# display.net
KiCad netlist of a schematic drawn in Altium Designer
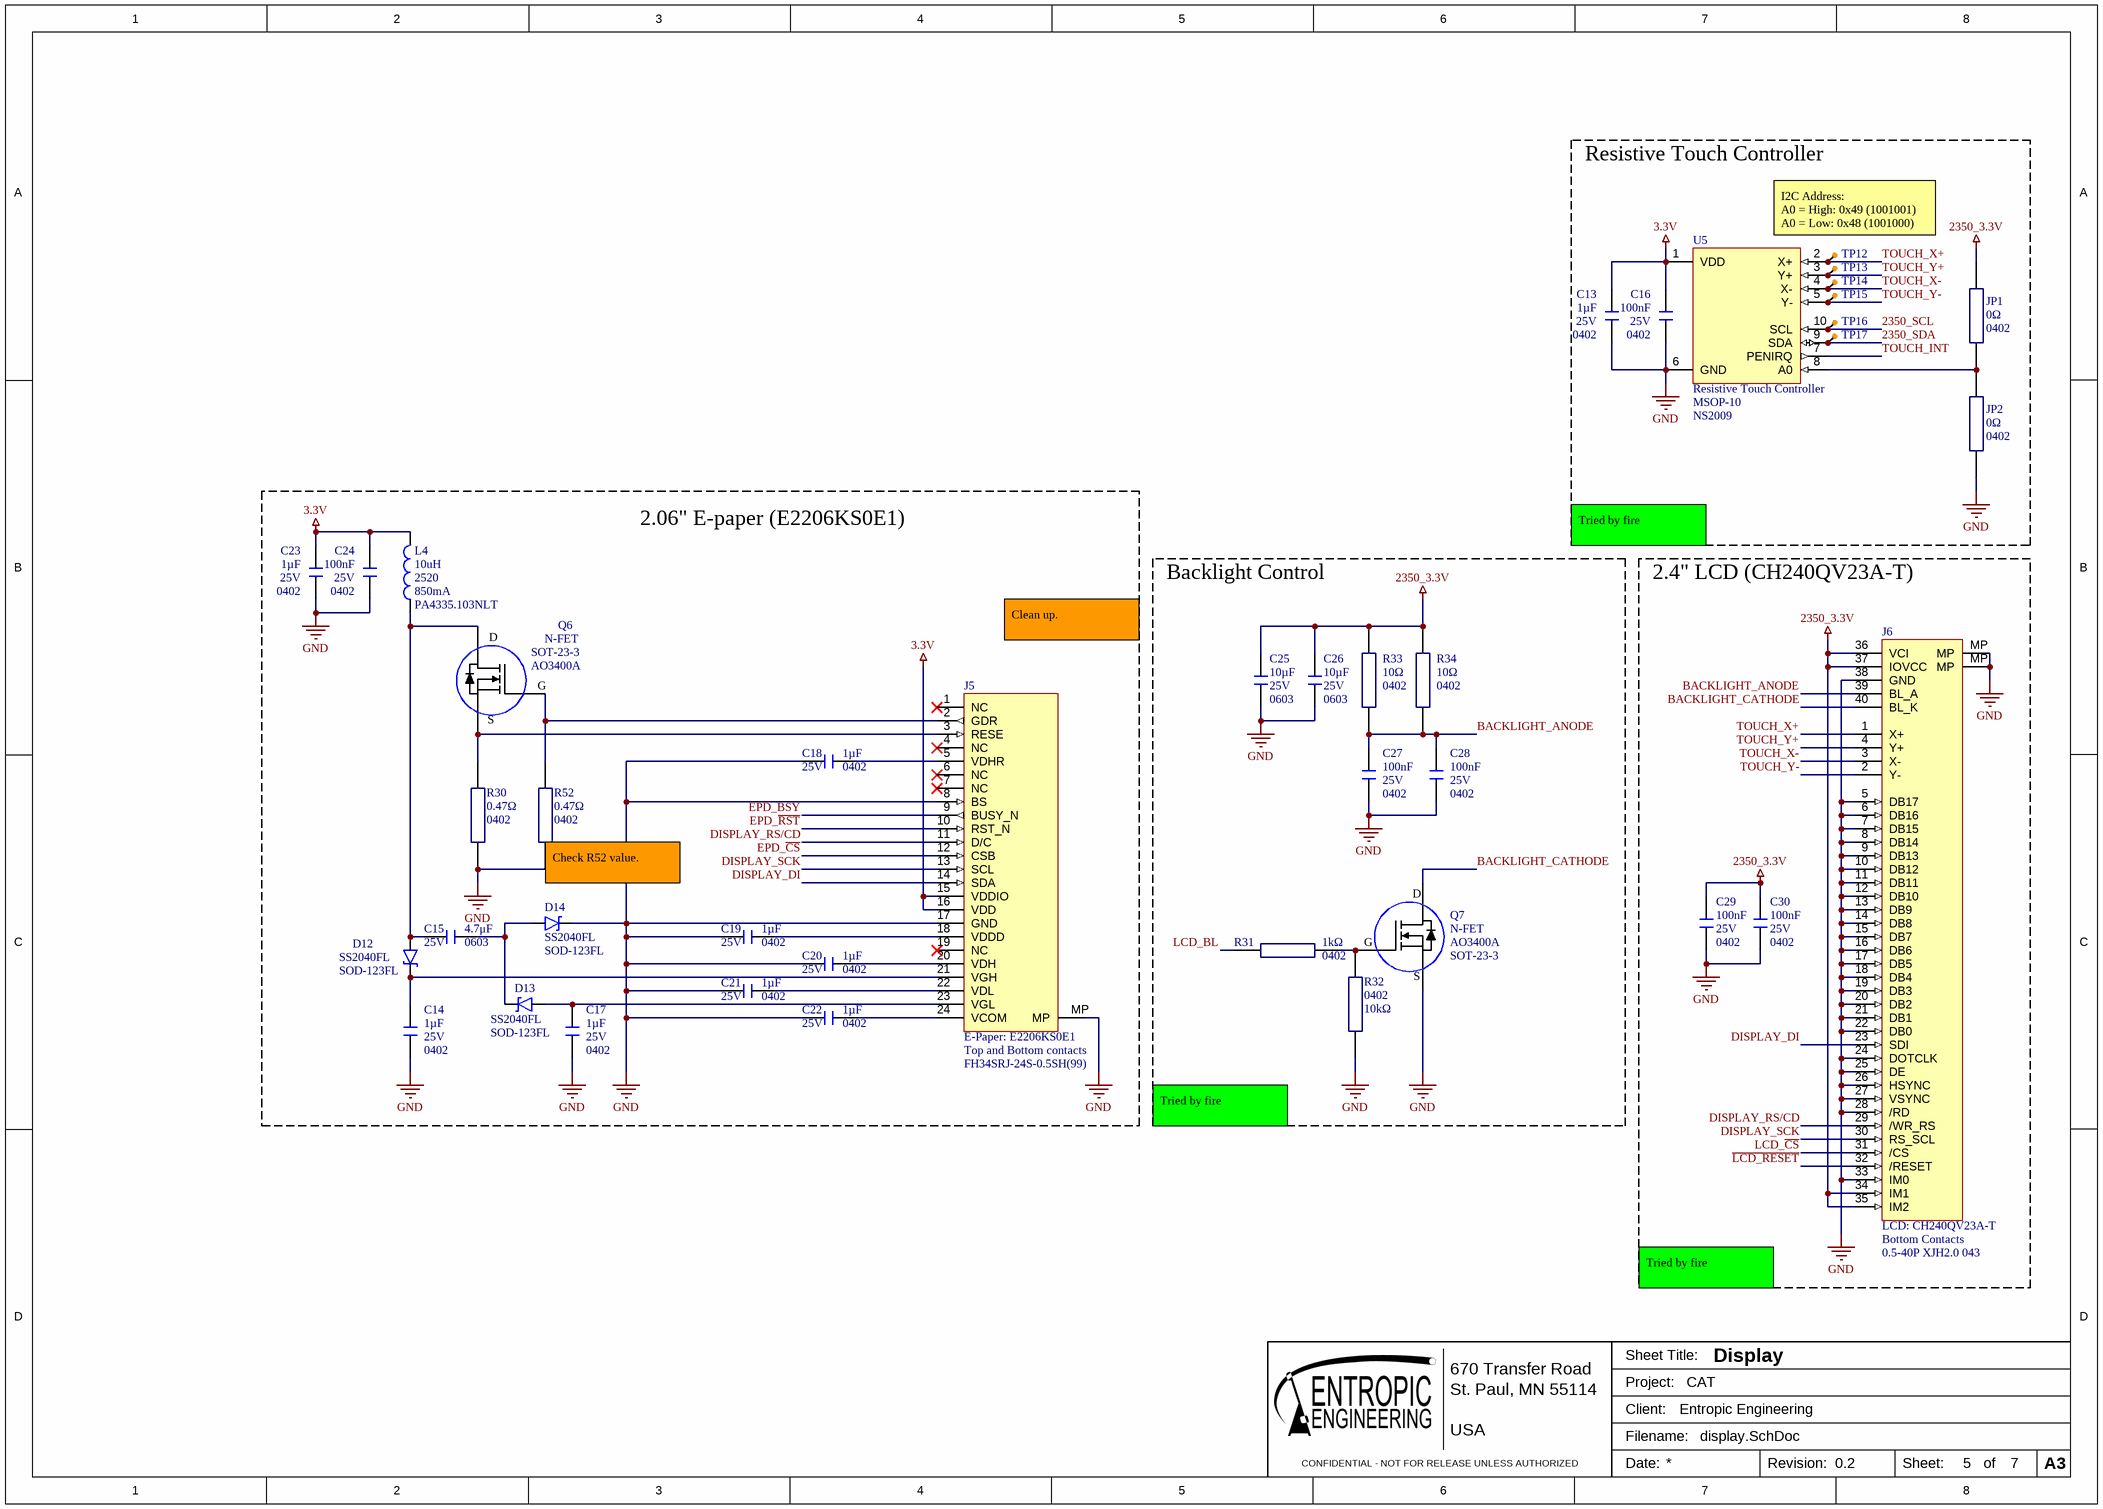
[diagram p0: display.SchDoc]

(export (version "E")
  (design (tool "Eeschema 10.0.6"))
  (components
    (comp (ref "C13")
      (value "GRM155R61E105KA12D")
      (footprint "0402_capacitor")
      (description "1 µF, 25 V, X5R, 0402 Chip capacitor")
      (fields
        (field (name "MANUFACTURER") "Murata")
        (field (name "HOUSE_PART_NUMBER") "C-1uF-0402-002")
        (field (name "SIZE CODE") "0402")
        (field (name "CAPACITANCE") "1µF")
        (field (name "VOLTAGE") "25V")
      )
      (libsource (lib "cat") (part "GRM155R61E105KA12D"))
    )
    (comp (ref "C14")
      (value "GRM155R61E105KA12D")
      (footprint "0402_capacitor")
      (description "1 µF, 25 V, X5R, 0402 Chip capacitor")
      (fields
        (field (name "MANUFACTURER") "Murata")
        (field (name "HOUSE_PART_NUMBER") "C-1uF-0402-002")
        (field (name "SIZE CODE") "0402")
        (field (name "CAPACITANCE") "1µF")
        (field (name "VOLTAGE") "25V")
      )
      (libsource (lib "cat") (part "GRM155R61E105KA12D"))
    )
    (comp (ref "C15")
      (value "4.7μF")
      (footprint "0603_capacitor")
      (description "4.7 μF, 25 V, X7R, 0603 Chip capacitor")
      (fields
        (field (name "MANUFACTURER") "TDK")
        (field (name "MANUFACTURER PART NUMBER") "C1608X5R1E475K080AC")
        (field (name "VOLTAGE RATING") "25V")
        (field (name "CASE/PACKAGE") "0603")
      )
      (libsource (lib "cat") (part "C1608X5R1E475K080AC"))
    )
    (comp (ref "C16")
      (value "GRM155R71E104KE14D")
      (footprint "0402_capacitor")
      (description "100 nF, 25 V, X7R, 0402 Chip capacitor")
      (fields
        (field (name "MANUFACTURER") "Murata")
        (field (name "TOLERANCE") "10%")
        (field (name "CASE CODE (IMPERIAL)") "0402")
        (field (name "VOLTAGE") "25V")
        (field (name "CAPACITANCE") "100nF")
      )
      (libsource (lib "") (part "GRM155R71E104KE14D_1"))
    )
    (comp (ref "C17")
      (value "GRM155R61E105KA12D")
      (footprint "0402_capacitor")
      (description "1 µF, 25 V, X5R, 0402 Chip capacitor")
      (fields
        (field (name "MANUFACTURER") "Murata")
        (field (name "HOUSE_PART_NUMBER") "C-1uF-0402-002")
        (field (name "SIZE CODE") "0402")
        (field (name "CAPACITANCE") "1µF")
        (field (name "VOLTAGE") "25V")
      )
      (libsource (lib "cat") (part "GRM155R61E105KA12D"))
    )
    (comp (ref "C18")
      (value "GRM155R61E105KA12D")
      (footprint "0402_capacitor")
      (description "1 µF, 25 V, X5R, 0402 Chip capacitor")
      (fields
        (field (name "MANUFACTURER") "Murata")
        (field (name "HOUSE_PART_NUMBER") "C-1uF-0402-002")
        (field (name "SIZE CODE") "0402")
        (field (name "CAPACITANCE") "1µF")
        (field (name "VOLTAGE") "25V")
      )
      (libsource (lib "cat") (part "GRM155R61E105KA12D"))
    )
    (comp (ref "C19")
      (value "GRM155R61E105KA12D")
      (footprint "0402_capacitor")
      (description "1 µF, 25 V, X5R, 0402 Chip capacitor")
      (fields
        (field (name "MANUFACTURER") "Murata")
        (field (name "HOUSE_PART_NUMBER") "C-1uF-0402-002")
        (field (name "SIZE CODE") "0402")
        (field (name "CAPACITANCE") "1µF")
        (field (name "VOLTAGE") "25V")
      )
      (libsource (lib "cat") (part "GRM155R61E105KA12D"))
    )
    (comp (ref "C20")
      (value "GRM155R61E105KA12D")
      (footprint "0402_capacitor")
      (description "1 µF, 25 V, X5R, 0402 Chip capacitor")
      (fields
        (field (name "MANUFACTURER") "Murata")
        (field (name "HOUSE_PART_NUMBER") "C-1uF-0402-002")
        (field (name "SIZE CODE") "0402")
        (field (name "CAPACITANCE") "1µF")
        (field (name "VOLTAGE") "25V")
      )
      (libsource (lib "cat") (part "GRM155R61E105KA12D"))
    )
    (comp (ref "C21")
      (value "GRM155R61E105KA12D")
      (footprint "0402_capacitor")
      (description "1 µF, 25 V, X5R, 0402 Chip capacitor")
      (fields
        (field (name "MANUFACTURER") "Murata")
        (field (name "HOUSE_PART_NUMBER") "C-1uF-0402-002")
        (field (name "SIZE CODE") "0402")
        (field (name "CAPACITANCE") "1µF")
        (field (name "VOLTAGE") "25V")
      )
      (libsource (lib "cat") (part "GRM155R61E105KA12D"))
    )
    (comp (ref "C22")
      (value "GRM155R61E105KA12D")
      (footprint "0402_capacitor")
      (description "1 µF, 25 V, X5R, 0402 Chip capacitor")
      (fields
        (field (name "MANUFACTURER") "Murata")
        (field (name "HOUSE_PART_NUMBER") "C-1uF-0402-002")
        (field (name "SIZE CODE") "0402")
        (field (name "CAPACITANCE") "1µF")
        (field (name "VOLTAGE") "25V")
      )
      (libsource (lib "cat") (part "GRM155R61E105KA12D"))
    )
    (comp (ref "C23")
      (value "GRM155R61E105KA12D")
      (footprint "0402_capacitor")
      (description "1 µF, 25 V, X5R, 0402 Chip capacitor")
      (fields
        (field (name "MANUFACTURER") "Murata")
        (field (name "HOUSE_PART_NUMBER") "C-1uF-0402-002")
        (field (name "SIZE CODE") "0402")
        (field (name "CAPACITANCE") "1µF")
        (field (name "VOLTAGE") "25V")
      )
      (libsource (lib "cat") (part "GRM155R61E105KA12D"))
    )
    (comp (ref "C24")
      (value "GRM155R71E104KE14D")
      (footprint "0402_capacitor")
      (description "100 nF, 25 V, X7R, 0402 Chip capacitor")
      (fields
        (field (name "MANUFACTURER") "Murata")
        (field (name "TOLERANCE") "10%")
        (field (name "CASE CODE (IMPERIAL)") "0402")
        (field (name "VOLTAGE") "25V")
        (field (name "CAPACITANCE") "100nF")
      )
      (libsource (lib "") (part "GRM155R71E104KE14D_1"))
    )
    (comp (ref "C25")
      (value "10µF")
      (footprint "0603_capacitor")
      (description "10 µF, 25 V, X5R, 0603 Chip capacitor")
      (fields
        (field (name "MANUFACTURER") "Samsung")
        (field (name "CASE/PACKAGE") "0603")
        (field (name "TOLERANCE") "20%")
        (field (name "VOLTAGE RATING") "25V")
      )
      (libsource (lib "cat") (part "CL10A106MA8NRNC"))
    )
    (comp (ref "C26")
      (value "10µF")
      (footprint "0603_capacitor")
      (description "10 µF, 25 V, X5R, 0603 Chip capacitor")
      (fields
        (field (name "MANUFACTURER") "Samsung")
        (field (name "CASE/PACKAGE") "0603")
        (field (name "TOLERANCE") "20%")
        (field (name "VOLTAGE RATING") "25V")
      )
      (libsource (lib "cat") (part "CL10A106MA8NRNC"))
    )
    (comp (ref "C27")
      (value "GRM155R71E104KE14D")
      (footprint "0402_capacitor")
      (description "100 nF, 25 V, X7R, 0402 Chip capacitor")
      (fields
        (field (name "MANUFACTURER") "Murata")
        (field (name "TOLERANCE") "10%")
        (field (name "CASE CODE (IMPERIAL)") "0402")
        (field (name "VOLTAGE") "25V")
        (field (name "CAPACITANCE") "100nF")
      )
      (libsource (lib "cat") (part "GRM155R71E104KE14D"))
    )
    (comp (ref "C28")
      (value "GRM155R71E104KE14D")
      (footprint "0402_capacitor")
      (description "100 nF, 25 V, X7R, 0402 Chip capacitor")
      (fields
        (field (name "MANUFACTURER") "Murata")
        (field (name "TOLERANCE") "10%")
        (field (name "CASE CODE (IMPERIAL)") "0402")
        (field (name "VOLTAGE") "25V")
        (field (name "CAPACITANCE") "100nF")
      )
      (libsource (lib "cat") (part "GRM155R71E104KE14D"))
    )
    (comp (ref "C29")
      (value "GRM155R71E104KE14D")
      (footprint "0402_capacitor")
      (description "100 nF, 25 V, X7R, 0402 Chip capacitor")
      (fields
        (field (name "MANUFACTURER") "Murata")
        (field (name "TOLERANCE") "10%")
        (field (name "CASE CODE (IMPERIAL)") "0402")
        (field (name "VOLTAGE") "25V")
        (field (name "CAPACITANCE") "100nF")
      )
      (libsource (lib "cat") (part "GRM155R71E104KE14D"))
    )
    (comp (ref "C30")
      (value "GRM155R71E104KE14D")
      (footprint "0402_capacitor")
      (description "100 nF, 25 V, X7R, 0402 Chip capacitor")
      (fields
        (field (name "MANUFACTURER") "Murata")
        (field (name "TOLERANCE") "10%")
        (field (name "CASE CODE (IMPERIAL)") "0402")
        (field (name "VOLTAGE") "25V")
        (field (name "CAPACITANCE") "100nF")
      )
      (libsource (lib "cat") (part "GRM155R71E104KE14D"))
    )
    (comp (ref "D12")
      (value "SS2040FL")
      (footprint "SOD-123")
      (description "Schottky-diode 2A 40V SOD123FL")
      (fields
        (field (name "MANUFACTURER") "Pan Jit")
        (field (name "MANUFACTURER PART NUMBER") "SS2040FL_R1_00001")
        (field (name "CASE/PACKAGE") "SOD-123FL")
      )
      (libsource (lib "cat") (part "SS2040FL_R1_00001"))
    )
    (comp (ref "D13")
      (value "SS2040FL")
      (footprint "SOD-123")
      (description "Schottky-diode 2A 40V SOD123FL")
      (fields
        (field (name "MANUFACTURER") "Pan Jit")
        (field (name "MANUFACTURER PART NUMBER") "SS2040FL_R1_00001")
        (field (name "CASE/PACKAGE") "SOD-123FL")
      )
      (libsource (lib "cat") (part "SS2040FL_R1_00001"))
    )
    (comp (ref "D14")
      (value "SS2040FL")
      (footprint "SOD-123")
      (description "Schottky-diode 2A 40V SOD123FL")
      (fields
        (field (name "MANUFACTURER") "Pan Jit")
        (field (name "MANUFACTURER PART NUMBER") "SS2040FL_R1_00001")
        (field (name "CASE/PACKAGE") "SOD-123FL")
      )
      (libsource (lib "cat") (part "SS2040FL_R1_00001"))
    )
    (comp (ref "J5")
      (value "E-Paper: E2206KS0E1")
      (footprint "E2206KS0E1")
      (description "24-Pin FPC Connector, 0.5mm pitch for E2206KS0E1 E-Paper display")
      (fields
        (field (name "MANUFACTURER") "Hirose")
        (field (name "CONTACT_SIDE") "Top and Bottom contacts")
        (field (name "MANUFACTURER PART NUMBER") "FH34SRJ-24S-0.5SH(99)")
      )
      (libsource (lib "cat") (part "FH34SRJ-24S-0.5SH"))
    )
    (comp (ref "J6")
      (value "LCD: CH240QV23A-T")
      (footprint "CH240QV23A-T")
      (description "40-Pin, 0.5 mm pitch, bottom contact, flat flex connector for LCD CH240QV23A-T")
      (fields
        (field (name "LCD PART NUMBER") "CH240QV23A-T")
        (field (name "CONTACT_SIDE") "Bottom Contacts")
        (field (name "MANUFACTURER PART NUMBER") "0.5-40P XJH2.0 043")
        (field (name "HOUSE_PART_NUMBER") "0.5-40P XJH2.0 043")
      )
      (libsource (lib "cat") (part "0.5-40P XJH2.0 043"))
    )
    (comp (ref "JP1")
      (value "0Ω")
      (footprint "0402_resistor")
      (description "0 Ω, 0402 Chip resistor (jumper)")
      (fields
        (field (name "MANUFACTURER") "Yageo")
        (field (name "MANUFACTURER PART NUMBER") "RC0402FR-070RL")
        (field (name "CASE/PACKAGE") "0402")
      )
      (libsource (lib "cat") (part "RC0402FR-070RL"))
    )
    (comp (ref "JP2")
      (value "0Ω")
      (footprint "0402_resistor")
      (description "0 Ω, 0402 Chip resistor (jumper)")
      (fields
        (field (name "MANUFACTURER") "Yageo")
        (field (name "MANUFACTURER PART NUMBER") "RC0402FR-070RL")
        (field (name "CASE/PACKAGE") "0402")
      )
      (libsource (lib "cat") (part "RC0402FR-070RL"))
    )
    (comp (ref "L4")
      (value "10uH")
      (footprint "INDC2520X12N")
      (description "Drum Core Shielded Power Inductor Wirewound Ferrite 10uH 20% 1MHz 0.85A SMD T/R")
      (fields
        (field (name "MANUFACTURER") "Pulse")
        (field (name "CASE/PACKAGE") "2520")
        (field (name "TOLERANCE") "20%")
        (field (name "CURRENT RATING") "850mA")
        (field (name "MANUFACTURER PART NUMBER") "PA4335.103NLT")
      )
      (libsource (lib "cat") (part "PA4335.103NLT"))
    )
    (comp (ref "Q6")
      (value "N-FET")
      (footprint "SOT95P280X115-3N")
      (description "N-FET, 30V, 5.7A, SOT-23-3")
      (fields
        (field (name "MANUFACTURER") "Alpha & Omega Semiconductor")
        (field (name "HOUSE_PART_NUMBER") "AO3400A")
        (field (name "CASE/PACKAGE") "SOT-23-3")
        (field (name "MANUFACTURER PART NUMBER") "AO3400A")
      )
      (libsource (lib "cat") (part "AO3400A"))
    )
    (comp (ref "Q7")
      (value "N-FET")
      (footprint "SOT95P280X115-3N")
      (description "N-FET, 30V, 5.7A, SOT-23-3")
      (fields
        (field (name "MANUFACTURER") "Alpha & Omega Semiconductor")
        (field (name "CASE/PACKAGE") "SOT-23-3")
        (field (name "MANUFACTURER PART NUMBER") "AO3400A")
        (field (name "HOUSE_PART_NUMBER") "AO3400A")
      )
      (libsource (lib "cat") (part "AO3400A"))
    )
    (comp (ref "R30")
      (value "0.47Ω")
      (footprint "0402_resistor")
      (description "0.47Ω, 1% 0402 Chip resistor")
      (fields
        (field (name "MANUFACTURER") "Yageo")
        (field (name "MANUFACTURER PART NUMBER") "RL0402FR-070R47L")
        (field (name "CASE/PACKAGE") "0402")
      )
      (libsource (lib "cat") (part "RL0402FR-070R47L"))
    )
    (comp (ref "R31")
      (value "1kΩ")
      (footprint "0402_resistor")
      (description "1 kΩ, 0402 Chip resistor")
      (fields
        (field (name "MANUFACTURER") "Yageo")
        (field (name "MANUFACTURER PART NUMBER") "RC0402JR-071KL")
        (field (name "CASE/PACKAGE") "0402")
      )
      (libsource (lib "cat") (part "RC0402JR-071KL"))
    )
    (comp (ref "R32")
      (value "10kΩ")
      (footprint "0402_resistor")
      (description "10 kΩ, 0402 Chip resistor")
      (fields
        (field (name "MANUFACTURER") "Yageo")
        (field (name "MANUFACTURER PART NUMBER") "RC0402FR-0710KL")
        (field (name "CASE CODE (IMPERIAL)") "0402")
      )
      (libsource (lib "cat") (part "RC0402FR-0710KL"))
    )
    (comp (ref "R33")
      (value "10Ω")
      (footprint "0402_resistor")
      (description "10 Ω, 0402 Chip resistor")
      (fields
        (field (name "MANUFACTURER") "Yageo")
        (field (name "TOLERANCE") "5%")
        (field (name "CASE/PACKAGE") "0402")
      )
      (libsource (lib "cat") (part "RC0402JR-0710RL"))
    )
    (comp (ref "R34")
      (value "10Ω")
      (footprint "0402_resistor")
      (description "10 Ω, 0402 Chip resistor")
      (fields
        (field (name "MANUFACTURER") "Yageo")
        (field (name "TOLERANCE") "5%")
        (field (name "CASE/PACKAGE") "0402")
      )
      (libsource (lib "cat") (part "RC0402JR-0710RL"))
    )
    (comp (ref "R52")
      (value "0.47Ω")
      (footprint "0402_resistor")
      (description "0.47Ω, 1% 0402 Chip resistor")
      (fields
        (field (name "MANUFACTURER") "Yageo")
        (field (name "MANUFACTURER PART NUMBER") "RL0402FR-070R47L")
        (field (name "CASE/PACKAGE") "0402")
      )
      (libsource (lib "cat") (part "RL0402FR-070R47L"))
    )
    (comp (ref "TP12")
      (value "test_point-1")
      (footprint "test_point-1")
      (description "Test point")
      (libsource (lib "cat") (part "test_point-1"))
    )
    (comp (ref "TP13")
      (value "test_point-1")
      (footprint "test_point-1")
      (description "Test point")
      (libsource (lib "cat") (part "test_point-1"))
    )
    (comp (ref "TP14")
      (value "test_point-1")
      (footprint "test_point-1")
      (description "Test point")
      (libsource (lib "cat") (part "test_point-1"))
    )
    (comp (ref "TP15")
      (value "test_point-1")
      (footprint "test_point-1")
      (description "Test point")
      (libsource (lib "cat") (part "test_point-1"))
    )
    (comp (ref "TP16")
      (value "SENSOR_SDA")
      (footprint "test_point-1")
      (description "Test point")
      (libsource (lib "cat") (part "test_point-1"))
    )
    (comp (ref "TP17")
      (value "SENSOR_SCL")
      (footprint "test_point-1")
      (description "Test point")
      (libsource (lib "cat") (part "test_point-1"))
    )
    (comp (ref "U5")
      (value "Resistive Touch Controller")
      (footprint "TSSOP50P490X112-10N")
      (fields
        (field (name "MANUFACTURER") "NSIWAY")
        (field (name "CASE/PACKAGE") "MSOP-10")
        (field (name "MANUFACTURER PART NUMBER") "NS2009")
        (field (name "HOUSE_PART_NUMBER") "NS2009")
      )
      (libsource (lib "cat") (part "NS2009"))
    )
  )
  (nets
    (net (code "1") (name "/2350_SCL") (class "Default")
      (node (ref "TP16") (pin "1") (pinfunction "1_1") (pintype "passive"))
      (node (ref "U5") (pin "10") (pinfunction "SCL_10") (pintype "input"))
    )
    (net (code "2") (name "/2350_SDA") (class "Default")
      (node (ref "TP17") (pin "1") (pinfunction "1_1") (pintype "passive"))
      (node (ref "U5") (pin "9") (pinfunction "SDA_9") (pintype "bidirectional"))
    )
    (net (code "3") (name "/BACKLIGHT_ANODE") (class "Default")
      (node (ref "C27") (pin "2") (pinfunction "2_2") (pintype "passive"))
      (node (ref "C28") (pin "2") (pinfunction "2_2") (pintype "passive"))
      (node (ref "J6") (pin "39") (pinfunction "BL_A_39") (pintype "power_in"))
      (node (ref "R33") (pin "1") (pinfunction "1_1") (pintype "passive"))
      (node (ref "R34") (pin "1") (pinfunction "1_1") (pintype "passive"))
    )
    (net (code "4") (name "/BACKLIGHT_CATHODE") (class "Default")
      (node (ref "J6") (pin "40") (pinfunction "BL_K_40") (pintype "power_in"))
      (node (ref "Q7") (pin "3") (pinfunction "D_3") (pintype "passive"))
    )
    (net (code "5") (name "/DISPLAY_DI") (class "Default")
      (node (ref "J5") (pin "14") (pinfunction "SDA_14") (pintype "input"))
      (node (ref "J6") (pin "23") (pinfunction "SDI_23") (pintype "input"))
    )
    (net (code "6") (name "/DISPLAY_RS{slash}CD") (class "Default")
      (node (ref "J5") (pin "11") (pinfunction "D/C_11") (pintype "input"))
      (node (ref "J6") (pin "29") (pinfunction "/WR_RS_29") (pintype "input"))
    )
    (net (code "7") (name "/DISPLAY_SCK") (class "Default")
      (node (ref "J5") (pin "13") (pinfunction "SCL_13") (pintype "input"))
      (node (ref "J6") (pin "30") (pinfunction "RS_SCL_30") (pintype "input"))
    )
    (net (code "8") (name "/EPD_~{BSY}") (class "Default")
      (node (ref "J5") (pin "9") (pinfunction "BUSY_N_9") (pintype "output"))
    )
    (net (code "9") (name "/EPD_~{CS}") (class "Default")
      (node (ref "J5") (pin "12") (pinfunction "CSB_12") (pintype "input"))
    )
    (net (code "10") (name "/EPD_~{RST}") (class "Default")
      (node (ref "J5") (pin "10") (pinfunction "RST_N_10") (pintype "input"))
    )
    (net (code "11") (name "/LCD_BL") (class "Default")
      (node (ref "R31") (pin "1") (pinfunction "1_1") (pintype "passive"))
    )
    (net (code "12") (name "/LCD_RESET") (class "Default")
      (node (ref "J6") (pin "32") (pinfunction "/RESET_32") (pintype "input"))
    )
    (net (code "13") (name "/LCD_~{CS}") (class "Default")
      (node (ref "J6") (pin "31") (pinfunction "/CS_31") (pintype "input"))
    )
    (net (code "14") (name "/TOUCH_INT") (class "Default")
      (node (ref "U5") (pin "7") (pinfunction "PENIRQ_7") (pintype "output"))
    )
    (net (code "15") (name "/TOUCH_X+") (class "Default")
      (node (ref "J6") (pin "1") (pinfunction "X+_1") (pintype "passive"))
      (node (ref "TP12") (pin "1") (pinfunction "1_1") (pintype "passive"))
      (node (ref "U5") (pin "2") (pinfunction "X+_2") (pintype "input"))
    )
    (net (code "16") (name "/TOUCH_X-") (class "Default")
      (node (ref "J6") (pin "3") (pinfunction "X-_3") (pintype "passive"))
      (node (ref "TP14") (pin "1") (pinfunction "1_1") (pintype "passive"))
      (node (ref "U5") (pin "4") (pinfunction "X-_4") (pintype "input"))
    )
    (net (code "17") (name "/TOUCH_Y+") (class "Default")
      (node (ref "J6") (pin "4") (pinfunction "Y+_4") (pintype "passive"))
      (node (ref "TP13") (pin "1") (pinfunction "1_1") (pintype "passive"))
      (node (ref "U5") (pin "3") (pinfunction "Y+_3") (pintype "input"))
    )
    (net (code "18") (name "/TOUCH_Y-") (class "Default")
      (node (ref "J6") (pin "2") (pinfunction "Y-_2") (pintype "passive"))
      (node (ref "TP15") (pin "1") (pinfunction "1_1") (pintype "passive"))
      (node (ref "U5") (pin "5") (pinfunction "Y-_5") (pintype "input"))
    )
    (net (code "19") (name "3.3V") (class "Default")
      (node (ref "C13") (pin "2") (pinfunction "2_2") (pintype "passive"))
      (node (ref "C16") (pin "2") (pinfunction "2_2") (pintype "passive"))
      (node (ref "C23") (pin "2") (pinfunction "2_2") (pintype "passive"))
      (node (ref "C24") (pin "2") (pinfunction "2_2") (pintype "passive"))
      (node (ref "J5") (pin "15") (pinfunction "VDDIO_15") (pintype "power_in"))
      (node (ref "J5") (pin "16") (pinfunction "VDD_16") (pintype "power_in"))
      (node (ref "L4") (pin "1") (pinfunction "1_1") (pintype "passive"))
      (node (ref "U5") (pin "1") (pinfunction "VDD_1") (pintype "power_in"))
    )
    (net (code "20") (name "2350_3.3V") (class "Default")
      (node (ref "C25") (pin "2") (pinfunction "2_2") (pintype "passive"))
      (node (ref "C26") (pin "2") (pinfunction "2_2") (pintype "passive"))
      (node (ref "C29") (pin "2") (pinfunction "2_2") (pintype "passive"))
      (node (ref "C30") (pin "2") (pinfunction "2_2") (pintype "passive"))
      (node (ref "J6") (pin "34") (pinfunction "IM1_34") (pintype "input"))
      (node (ref "J6") (pin "35") (pinfunction "IM2_35") (pintype "input"))
      (node (ref "J6") (pin "36") (pinfunction "VCI_36") (pintype "power_in"))
      (node (ref "J6") (pin "37") (pinfunction "IOVCC_37") (pintype "power_in"))
      (node (ref "JP1") (pin "1") (pinfunction "1_1") (pintype "passive"))
      (node (ref "R33") (pin "2") (pinfunction "2_2") (pintype "passive"))
      (node (ref "R34") (pin "2") (pinfunction "2_2") (pintype "passive"))
    )
    (net (code "21") (name "GND") (class "Default")
      (node (ref "C13") (pin "1") (pinfunction "1_1") (pintype "passive"))
      (node (ref "C14") (pin "1") (pinfunction "1_1") (pintype "passive"))
      (node (ref "C16") (pin "1") (pinfunction "1_1") (pintype "passive"))
      (node (ref "C17") (pin "1") (pinfunction "1_1") (pintype "passive"))
      (node (ref "C18") (pin "1") (pinfunction "1_1") (pintype "passive"))
      (node (ref "C19") (pin "1") (pinfunction "1_1") (pintype "passive"))
      (node (ref "C20") (pin "1") (pinfunction "1_1") (pintype "passive"))
      (node (ref "C21") (pin "1") (pinfunction "1_1") (pintype "passive"))
      (node (ref "C22") (pin "1") (pinfunction "1_1") (pintype "passive"))
      (node (ref "C23") (pin "1") (pinfunction "1_1") (pintype "passive"))
      (node (ref "C24") (pin "1") (pinfunction "1_1") (pintype "passive"))
      (node (ref "C25") (pin "1") (pinfunction "1_1") (pintype "passive"))
      (node (ref "C26") (pin "1") (pinfunction "1_1") (pintype "passive"))
      (node (ref "C27") (pin "1") (pinfunction "1_1") (pintype "passive"))
      (node (ref "C28") (pin "1") (pinfunction "1_1") (pintype "passive"))
      (node (ref "C29") (pin "1") (pinfunction "1_1") (pintype "passive"))
      (node (ref "C30") (pin "1") (pinfunction "1_1") (pintype "passive"))
      (node (ref "D14") (pin "K") (pinfunction "K_K") (pintype "passive"))
      (node (ref "J5") (pin "17") (pinfunction "GND_17") (pintype "power_in"))
      (node (ref "J5") (pin "8") (pinfunction "BS_8") (pintype "input"))
      (node (ref "J5") (pin "MP") (pinfunction "MP_MP") (pintype "passive"))
      (node (ref "J6") (pin "10") (pinfunction "DB12_10") (pintype "input"))
      (node (ref "J6") (pin "11") (pinfunction "DB11_11") (pintype "input"))
      (node (ref "J6") (pin "12") (pinfunction "DB10_12") (pintype "input"))
      (node (ref "J6") (pin "13") (pinfunction "DB9_13") (pintype "input"))
      (node (ref "J6") (pin "14") (pinfunction "DB8_14") (pintype "input"))
      (node (ref "J6") (pin "15") (pinfunction "DB7_15") (pintype "input"))
      (node (ref "J6") (pin "16") (pinfunction "DB6_16") (pintype "input"))
      (node (ref "J6") (pin "17") (pinfunction "DB5_17") (pintype "input"))
      (node (ref "J6") (pin "18") (pinfunction "DB4_18") (pintype "input"))
      (node (ref "J6") (pin "19") (pinfunction "DB3_19") (pintype "input"))
      (node (ref "J6") (pin "20") (pinfunction "DB2_20") (pintype "input"))
      (node (ref "J6") (pin "21") (pinfunction "DB1_21") (pintype "input"))
      (node (ref "J6") (pin "22") (pinfunction "DB0_22") (pintype "input"))
      (node (ref "J6") (pin "24") (pinfunction "DOTCLK_24") (pintype "input"))
      (node (ref "J6") (pin "25") (pinfunction "DE_25") (pintype "input"))
      (node (ref "J6") (pin "26") (pinfunction "HSYNC_26") (pintype "input"))
      (node (ref "J6") (pin "27") (pinfunction "VSYNC_27") (pintype "input"))
      (node (ref "J6") (pin "28") (pinfunction "/RD_28") (pintype "input"))
      (node (ref "J6") (pin "33") (pinfunction "IM0_33") (pintype "input"))
      (node (ref "J6") (pin "38") (pinfunction "GND_38") (pintype "power_in"))
      (node (ref "J6") (pin "5") (pinfunction "DB17_5") (pintype "input"))
      (node (ref "J6") (pin "6") (pinfunction "DB16_6") (pintype "input"))
      (node (ref "J6") (pin "7") (pinfunction "DB15_7") (pintype "input"))
      (node (ref "J6") (pin "8") (pinfunction "DB14_8") (pintype "input"))
      (node (ref "J6") (pin "9") (pinfunction "DB13_9") (pintype "input"))
      (node (ref "J6") (pin "MP") (pinfunction "MP_MP") (pintype "passive"))
      (node (ref "JP2") (pin "2") (pinfunction "2_2") (pintype "passive"))
      (node (ref "Q7") (pin "2") (pinfunction "S_2") (pintype "passive"))
      (node (ref "R30") (pin "1") (pinfunction "1_1") (pintype "passive"))
      (node (ref "R32") (pin "2") (pinfunction "2_2") (pintype "passive"))
      (node (ref "R52") (pin "1") (pinfunction "1_1") (pintype "passive"))
      (node (ref "U5") (pin "6") (pinfunction "GND_6") (pintype "power_in"))
    )
    (net (code "22") (name "Net-(C15-Pad2)") (class "Default")
      (node (ref "C15") (pin "2") (pinfunction "2_2") (pintype "passive"))
      (node (ref "D13") (pin "K") (pinfunction "K_K") (pintype "passive"))
      (node (ref "D14") (pin "A") (pinfunction "A_A") (pintype "passive"))
    )
    (net (code "23") (name "Net-(J5-GDR)") (class "Default")
      (node (ref "J5") (pin "2") (pinfunction "GDR_2") (pintype "output"))
      (node (ref "Q6") (pin "1") (pinfunction "G_1") (pintype "passive"))
      (node (ref "R52") (pin "2") (pinfunction "2_2") (pintype "passive"))
    )
    (net (code "24") (name "Net-(J5-RESE)") (class "Default")
      (node (ref "J5") (pin "3") (pinfunction "RESE_3") (pintype "input"))
      (node (ref "Q6") (pin "2") (pinfunction "S_2") (pintype "passive"))
      (node (ref "R30") (pin "2") (pinfunction "2_2") (pintype "passive"))
    )
    (net (code "25") (name "Net-(J5-VCOM)") (class "Default")
      (node (ref "C22") (pin "2") (pinfunction "2_2") (pintype "passive"))
      (node (ref "J5") (pin "24") (pinfunction "VCOM_24") (pintype "power_in"))
    )
    (net (code "26") (name "Net-(J5-VDDD)") (class "Default")
      (node (ref "C19") (pin "2") (pinfunction "2_2") (pintype "passive"))
      (node (ref "J5") (pin "18") (pinfunction "VDDD_18") (pintype "power_in"))
    )
    (net (code "27") (name "Net-(J5-VDH)") (class "Default")
      (node (ref "C20") (pin "2") (pinfunction "2_2") (pintype "passive"))
      (node (ref "J5") (pin "20") (pinfunction "VDH_20") (pintype "power_in"))
    )
    (net (code "28") (name "Net-(J5-VDHR)") (class "Default")
      (node (ref "C18") (pin "2") (pinfunction "2_2") (pintype "passive"))
      (node (ref "J5") (pin "5") (pinfunction "VDHR_5") (pintype "power_in"))
    )
    (net (code "29") (name "Net-(J5-VDL)") (class "Default")
      (node (ref "C21") (pin "2") (pinfunction "2_2") (pintype "passive"))
      (node (ref "J5") (pin "22") (pinfunction "VDL_22") (pintype "power_in"))
    )
    (net (code "30") (name "Net-(J5-VGH)") (class "Default")
      (node (ref "C14") (pin "2") (pinfunction "2_2") (pintype "passive"))
      (node (ref "D12") (pin "K") (pinfunction "K_K") (pintype "passive"))
      (node (ref "J5") (pin "21") (pinfunction "VGH_21") (pintype "power_in"))
    )
    (net (code "31") (name "Net-(J5-VGL)") (class "Default")
      (node (ref "C17") (pin "2") (pinfunction "2_2") (pintype "passive"))
      (node (ref "D13") (pin "A") (pinfunction "A_A") (pintype "passive"))
      (node (ref "J5") (pin "23") (pinfunction "VGL_23") (pintype "power_in"))
    )
    (net (code "32") (name "Net-(Q6-D)") (class "Default")
      (node (ref "C15") (pin "1") (pinfunction "1_1") (pintype "passive"))
      (node (ref "D12") (pin "A") (pinfunction "A_A") (pintype "passive"))
      (node (ref "L4") (pin "2") (pinfunction "2_2") (pintype "passive"))
      (node (ref "Q6") (pin "3") (pinfunction "D_3") (pintype "passive"))
    )
    (net (code "33") (name "Net-(Q7-G)") (class "Default")
      (node (ref "Q7") (pin "1") (pinfunction "G_1") (pintype "passive"))
      (node (ref "R31") (pin "2") (pinfunction "2_2") (pintype "passive"))
      (node (ref "R32") (pin "1") (pinfunction "1_1") (pintype "passive"))
    )
    (net (code "34") (name "Net-(U5-A0)") (class "Default")
      (node (ref "JP1") (pin "2") (pinfunction "2_2") (pintype "passive"))
      (node (ref "JP2") (pin "1") (pinfunction "1_1") (pintype "passive"))
      (node (ref "U5") (pin "8") (pinfunction "A0_8") (pintype "input"))
    )
    (net (code "35") (name "unconnected-(J5-NC-Pad1)") (class "Default")
      (node (ref "J5") (pin "1") (pinfunction "NC_1") (pintype "passive+no_connect"))
    )
    (net (code "36") (name "unconnected-(J5-NC-Pad4)") (class "Default")
      (node (ref "J5") (pin "4") (pinfunction "NC_4") (pintype "passive+no_connect"))
    )
    (net (code "37") (name "unconnected-(J5-NC-Pad6)") (class "Default")
      (node (ref "J5") (pin "6") (pinfunction "NC_6") (pintype "passive+no_connect"))
    )
    (net (code "38") (name "unconnected-(J5-NC-Pad7)") (class "Default")
      (node (ref "J5") (pin "7") (pinfunction "NC_7") (pintype "passive+no_connect"))
    )
    (net (code "39") (name "unconnected-(J5-NC-Pad19)") (class "Default")
      (node (ref "J5") (pin "19") (pinfunction "NC_19") (pintype "passive+no_connect"))
    )
  )
)
